# GyroAccelHeaders.net
KiCad netlist of a schematic drawn in Altium Designer
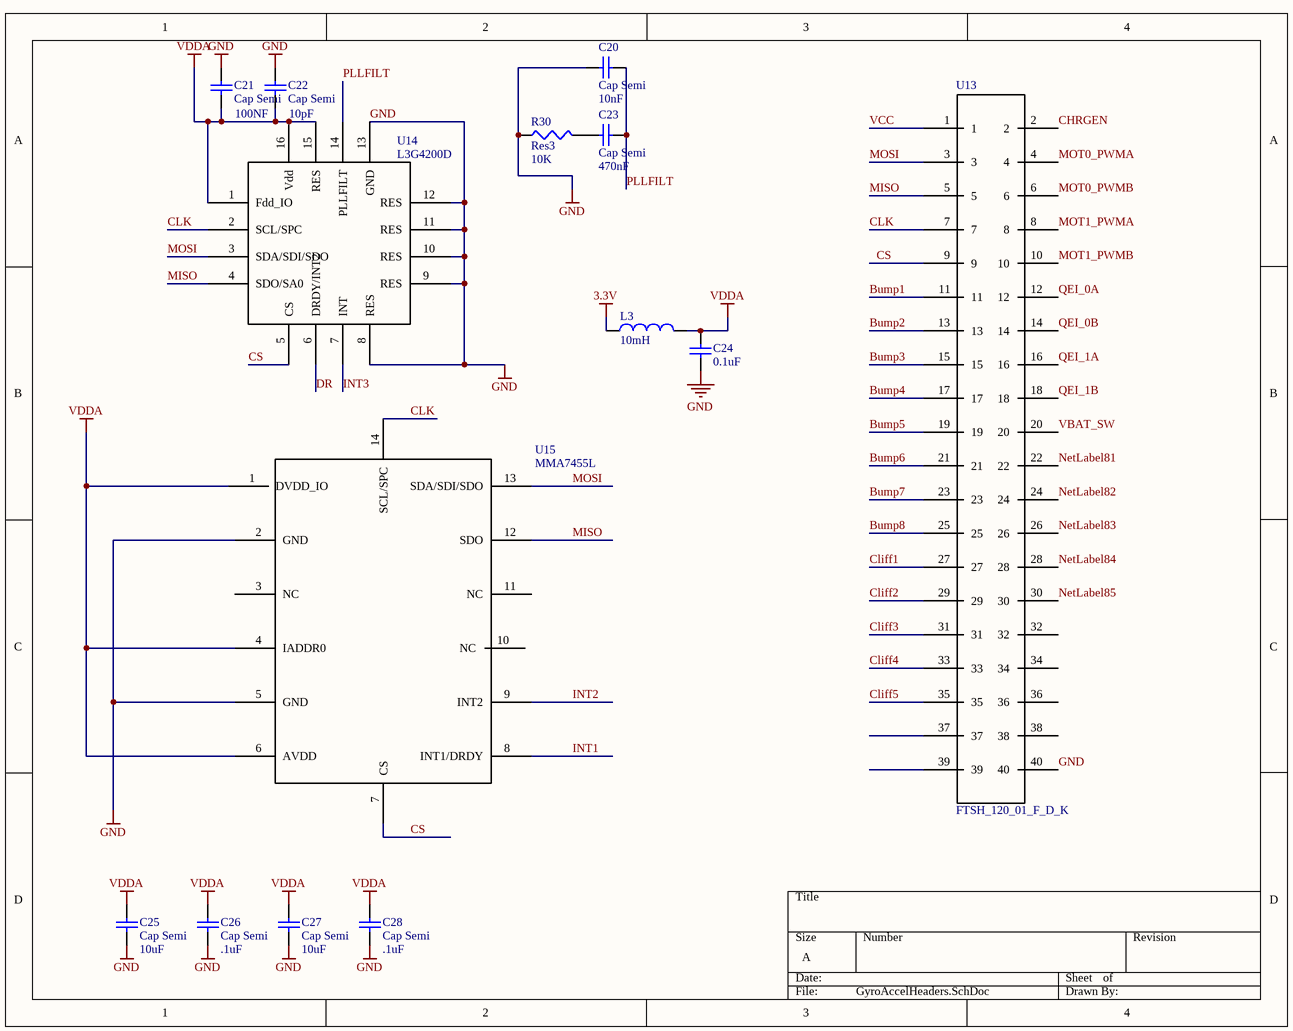
[diagram p0: GyroAccelHeaders.SchDoc]

(export (version "E")
  (design (tool "Eeschema 10.0.6"))
  (components
    (comp (ref "C20")
      (value "Cap Semi")
      (footprint "CAPC3216L")
      (description "Capacitor (Semiconductor SIM Model)")
      (fields (field (name "ALTIUM_VALUE") "10nF") (field (name "PUBLISHER") "Altium Limited"))
      (libsource (lib "Miscellaneous Devices") (part "Cap Semi"))
    )
    (comp (ref "C21")
      (value "Cap Semi")
      (footprint "CAPC3216L")
      (description "Capacitor (Semiconductor SIM Model)")
      (fields (field (name "ALTIUM_VALUE") "100NF") (field (name "PUBLISHER") "Altium Limited"))
      (libsource (lib "Miscellaneous Devices") (part "Cap Semi"))
    )
    (comp (ref "C22")
      (value "Cap Semi")
      (footprint "CAPC3216L")
      (description "Capacitor (Semiconductor SIM Model)")
      (fields (field (name "ALTIUM_VALUE") "10pF") (field (name "PUBLISHER") "Altium Limited"))
      (libsource (lib "Miscellaneous Devices") (part "Cap Semi"))
    )
    (comp (ref "C23")
      (value "Cap Semi")
      (footprint "CAPC3216L")
      (description "Capacitor (Semiconductor SIM Model)")
      (fields (field (name "ALTIUM_VALUE") "470nF") (field (name "PUBLISHER") "Altium Limited"))
      (libsource (lib "Miscellaneous Devices") (part "Cap Semi"))
    )
    (comp (ref "C24")
      (value "0.1uF")
      (footprint "CAPC1005L")
      (description "Capacitor (Semiconductor SIM Model)")
      (fields (field (name "Comment") "Cap Semi") (field (name "PUBLISHER") "Altium Limited"))
      (libsource (lib "Miscellaneous Devices") (part "Cap Semi"))
    )
    (comp (ref "C25")
      (value "Cap Semi")
      (footprint "CAPC3216L")
      (description "Capacitor (Semiconductor SIM Model)")
      (fields (field (name "ALTIUM_VALUE") "10uF") (field (name "PUBLISHER") "Altium Limited"))
      (libsource (lib "Miscellaneous Devices") (part "Cap Semi"))
    )
    (comp (ref "C26")
      (value "Cap Semi")
      (footprint "CAPC3216L")
      (description "Capacitor (Semiconductor SIM Model)")
      (fields (field (name "ALTIUM_VALUE") ".1uF") (field (name "PUBLISHER") "Altium Limited"))
      (libsource (lib "Miscellaneous Devices") (part "Cap Semi"))
    )
    (comp (ref "C27")
      (value "Cap Semi")
      (footprint "CAPC3216L")
      (description "Capacitor (Semiconductor SIM Model)")
      (fields (field (name "ALTIUM_VALUE") "10uF") (field (name "PUBLISHER") "Altium Limited"))
      (libsource (lib "Miscellaneous Devices") (part "Cap Semi"))
    )
    (comp (ref "C28")
      (value "Cap Semi")
      (footprint "CAPC3216L")
      (description "Capacitor (Semiconductor SIM Model)")
      (fields (field (name "ALTIUM_VALUE") ".1uF") (field (name "PUBLISHER") "Altium Limited"))
      (libsource (lib "Miscellaneous Devices") (part "Cap Semi"))
    )
    (comp (ref "L3")
      (value "10mH")
      (footprint "INDC2012L")
      (description "Inductor")
      (fields (field (name "PUBLISHER") "Altium Limited"))
      (libsource (lib "Miscellaneous Devices") (part "Inductor"))
    )
    (comp (ref "R30")
      (value "Res3")
      (footprint "RESC1608L")
      (description "Resistor")
      (fields (field (name "ALTIUM_VALUE") "10K") (field (name "PUBLISHER") "Altium Limited"))
      (libsource (lib "Miscellaneous Devices") (part "Res3"))
    )
    (comp (ref "U13")
      (value "FTSH_120_01_F_D_K")
      (footprint "FTSH_120_01_F_D_K")
      (description "Header, 2X20, 50mil, IDC")
      (libsource (lib "mrone") (part "FTSH_120_01_F_D_K"))
    )
    (comp (ref "U14")
      (value "L3G4200D")
      (footprint "L3G4200D")
      (description "3axis gyroscope, SPI")
      (libsource (lib "mrone") (part "L3G4200D"))
    )
    (comp (ref "U15")
      (value "MMA7455L")
      (footprint "MMA7455L")
      (description "3axis accelerometer")
      (libsource (lib "mrone") (part "MMA7455L"))
    )
  )
  (nets
    (net (code "1") (name "/Bump1") (class "Default")
      (node (ref "U13") (pin "11") (pinfunction "11_11") (pintype "passive"))
    )
    (net (code "2") (name "/Bump2") (class "Default")
      (node (ref "U13") (pin "13") (pinfunction "13_13") (pintype "passive"))
    )
    (net (code "3") (name "/Bump3") (class "Default")
      (node (ref "U13") (pin "15") (pinfunction "15_15") (pintype "passive"))
    )
    (net (code "4") (name "/Bump4") (class "Default")
      (node (ref "U13") (pin "17") (pinfunction "17_17") (pintype "passive"))
    )
    (net (code "5") (name "/Bump5") (class "Default")
      (node (ref "U13") (pin "19") (pinfunction "19_19") (pintype "passive"))
    )
    (net (code "6") (name "/Bump6") (class "Default")
      (node (ref "U13") (pin "21") (pinfunction "21_21") (pintype "passive"))
    )
    (net (code "7") (name "/Bump7") (class "Default")
      (node (ref "U13") (pin "23") (pinfunction "23_23") (pintype "passive"))
    )
    (net (code "8") (name "/Bump8") (class "Default")
      (node (ref "U13") (pin "25") (pinfunction "25_25") (pintype "passive"))
    )
    (net (code "9") (name "/CHRGEN") (class "Default")
      (node (ref "U13") (pin "2") (pinfunction "2_2") (pintype "passive"))
    )
    (net (code "10") (name "/CLK") (class "Default")
      (node (ref "U13") (pin "7") (pinfunction "7_7") (pintype "passive"))
      (node (ref "U14") (pin "2") (pinfunction "SCL/SPC_2") (pintype "passive"))
      (node (ref "U15") (pin "14") (pinfunction "SCL/SPC_14") (pintype "passive"))
    )
    (net (code "11") (name "/CS") (class "Default")
      (node (ref "U13") (pin "9") (pinfunction "9_9") (pintype "passive"))
      (node (ref "U14") (pin "5") (pinfunction "CS_5") (pintype "passive"))
      (node (ref "U15") (pin "7") (pinfunction "CS_7") (pintype "passive"))
    )
    (net (code "12") (name "/Cliff1") (class "Default")
      (node (ref "U13") (pin "27") (pinfunction "27_27") (pintype "passive"))
    )
    (net (code "13") (name "/Cliff2") (class "Default")
      (node (ref "U13") (pin "29") (pinfunction "29_29") (pintype "passive"))
    )
    (net (code "14") (name "/Cliff3") (class "Default")
      (node (ref "U13") (pin "31") (pinfunction "31_31") (pintype "passive"))
    )
    (net (code "15") (name "/Cliff4") (class "Default")
      (node (ref "U13") (pin "33") (pinfunction "33_33") (pintype "passive"))
    )
    (net (code "16") (name "/Cliff5") (class "Default")
      (node (ref "U13") (pin "35") (pinfunction "35_35") (pintype "passive"))
    )
    (net (code "17") (name "/DR") (class "Default")
      (node (ref "U14") (pin "6") (pinfunction "DRDY/INT2_6") (pintype "passive"))
    )
    (net (code "18") (name "/INT1") (class "Default")
      (node (ref "U15") (pin "8") (pinfunction "INT1/DRDY_8") (pintype "passive"))
    )
    (net (code "19") (name "/INT2") (class "Default")
      (node (ref "U15") (pin "9") (pinfunction "INT2_9") (pintype "passive"))
    )
    (net (code "20") (name "/INT3") (class "Default")
      (node (ref "U14") (pin "7") (pinfunction "INT_7") (pintype "passive"))
    )
    (net (code "21") (name "/MISO") (class "Default")
      (node (ref "U13") (pin "5") (pinfunction "5_5") (pintype "passive"))
      (node (ref "U14") (pin "4") (pinfunction "SDO/SA0_4") (pintype "passive"))
      (node (ref "U15") (pin "12") (pinfunction "SDO_12") (pintype "passive"))
    )
    (net (code "22") (name "/MOSI") (class "Default")
      (node (ref "U13") (pin "3") (pinfunction "3_3") (pintype "passive"))
      (node (ref "U14") (pin "3") (pinfunction "SDA/SDI/SDO_3") (pintype "passive"))
      (node (ref "U15") (pin "13") (pinfunction "SDA/SDI/SDO_13") (pintype "passive"))
    )
    (net (code "23") (name "/MOT0_PWMA") (class "Default")
      (node (ref "U13") (pin "4") (pinfunction "4_4") (pintype "passive"))
    )
    (net (code "24") (name "/MOT0_PWMB") (class "Default")
      (node (ref "U13") (pin "6") (pinfunction "6_6") (pintype "passive"))
    )
    (net (code "25") (name "/MOT1_PWMA") (class "Default")
      (node (ref "U13") (pin "8") (pinfunction "8_8") (pintype "passive"))
    )
    (net (code "26") (name "/MOT1_PWMB") (class "Default")
      (node (ref "U13") (pin "10") (pinfunction "10_10") (pintype "passive"))
    )
    (net (code "27") (name "/NetLabel81") (class "Default")
      (node (ref "U13") (pin "22") (pinfunction "22_22") (pintype "passive"))
    )
    (net (code "28") (name "/NetLabel82") (class "Default")
      (node (ref "U13") (pin "24") (pinfunction "24_24") (pintype "passive"))
    )
    (net (code "29") (name "/NetLabel83") (class "Default")
      (node (ref "U13") (pin "26") (pinfunction "26_26") (pintype "passive"))
    )
    (net (code "30") (name "/NetLabel84") (class "Default")
      (node (ref "U13") (pin "28") (pinfunction "28_28") (pintype "passive"))
    )
    (net (code "31") (name "/NetLabel85") (class "Default")
      (node (ref "U13") (pin "30") (pinfunction "30_30") (pintype "passive"))
    )
    (net (code "32") (name "/PLLFILT") (class "Default")
      (node (ref "C20") (pin "2") (pinfunction "2_2") (pintype "passive"))
      (node (ref "C23") (pin "2") (pinfunction "2_2") (pintype "passive"))
      (node (ref "U14") (pin "14") (pinfunction "PLLFILT_14") (pintype "passive"))
    )
    (net (code "33") (name "/QEI_0A") (class "Default")
      (node (ref "U13") (pin "12") (pinfunction "12_12") (pintype "passive"))
    )
    (net (code "34") (name "/QEI_0B") (class "Default")
      (node (ref "U13") (pin "14") (pinfunction "14_14") (pintype "passive"))
    )
    (net (code "35") (name "/QEI_1A") (class "Default")
      (node (ref "U13") (pin "16") (pinfunction "16_16") (pintype "passive"))
    )
    (net (code "36") (name "/QEI_1B") (class "Default")
      (node (ref "U13") (pin "18") (pinfunction "18_18") (pintype "passive"))
    )
    (net (code "37") (name "/VBAT_SW") (class "Default")
      (node (ref "U13") (pin "20") (pinfunction "20_20") (pintype "passive"))
    )
    (net (code "38") (name "/VCC") (class "Default")
      (node (ref "U13") (pin "1") (pinfunction "1_1") (pintype "passive"))
    )
    (net (code "39") (name "3.3V") (class "Default")
      (node (ref "L3") (pin "2") (pinfunction "2_2") (pintype "passive"))
    )
    (net (code "40") (name "GND") (class "Default")
      (node (ref "C20") (pin "1") (pinfunction "1_1") (pintype "passive"))
      (node (ref "C21") (pin "2") (pinfunction "2_2") (pintype "passive"))
      (node (ref "C22") (pin "2") (pinfunction "2_2") (pintype "passive"))
      (node (ref "C24") (pin "1") (pinfunction "1_1") (pintype "passive"))
      (node (ref "C25") (pin "1") (pinfunction "1_1") (pintype "passive"))
      (node (ref "C26") (pin "1") (pinfunction "1_1") (pintype "passive"))
      (node (ref "C27") (pin "1") (pinfunction "1_1") (pintype "passive"))
      (node (ref "C28") (pin "1") (pinfunction "1_1") (pintype "passive"))
      (node (ref "R30") (pin "1") (pinfunction "1_1") (pintype "passive"))
      (node (ref "U13") (pin "40") (pinfunction "40_40") (pintype "passive"))
      (node (ref "U14") (pin "10") (pinfunction "RES_10") (pintype "passive"))
      (node (ref "U14") (pin "11") (pinfunction "RES_11") (pintype "passive"))
      (node (ref "U14") (pin "12") (pinfunction "RES_12") (pintype "passive"))
      (node (ref "U14") (pin "13") (pinfunction "GND_13") (pintype "passive"))
      (node (ref "U14") (pin "8") (pinfunction "RES_8") (pintype "passive"))
      (node (ref "U14") (pin "9") (pinfunction "RES_9") (pintype "passive"))
      (node (ref "U15") (pin "2") (pinfunction "GND_2") (pintype "passive"))
      (node (ref "U15") (pin "5") (pinfunction "GND_5") (pintype "passive"))
    )
    (net (code "41") (name "Net-(C23-Pad1)") (class "Default")
      (node (ref "C23") (pin "1") (pinfunction "1_1") (pintype "passive"))
      (node (ref "R30") (pin "2") (pinfunction "2_2") (pintype "passive"))
    )
    (net (code "42") (name "VDDA") (class "Default")
      (node (ref "C21") (pin "1") (pinfunction "1_1") (pintype "passive"))
      (node (ref "C22") (pin "1") (pinfunction "1_1") (pintype "passive"))
      (node (ref "C24") (pin "2") (pinfunction "2_2") (pintype "passive"))
      (node (ref "C25") (pin "2") (pinfunction "2_2") (pintype "passive"))
      (node (ref "C26") (pin "2") (pinfunction "2_2") (pintype "passive"))
      (node (ref "C27") (pin "2") (pinfunction "2_2") (pintype "passive"))
      (node (ref "C28") (pin "2") (pinfunction "2_2") (pintype "passive"))
      (node (ref "L3") (pin "1") (pinfunction "1_1") (pintype "passive"))
      (node (ref "U14") (pin "1") (pinfunction "Fdd_IO_1") (pintype "passive"))
      (node (ref "U14") (pin "15") (pinfunction "RES_15") (pintype "passive"))
      (node (ref "U14") (pin "16") (pinfunction "Vdd_16") (pintype "passive"))
      (node (ref "U15") (pin "1") (pinfunction "DVDD_IO_1") (pintype "passive"))
      (node (ref "U15") (pin "4") (pinfunction "IADDR0_4") (pintype "passive"))
      (node (ref "U15") (pin "6") (pinfunction "AVDD_6") (pintype "passive"))
    )
    (net (code "43") (name "unconnected-(U13-Pad32)") (class "Default")
      (node (ref "U13") (pin "32") (pinfunction "32_32") (pintype "passive"))
    )
    (net (code "44") (name "unconnected-(U13-Pad34)") (class "Default")
      (node (ref "U13") (pin "34") (pinfunction "34_34") (pintype "passive"))
    )
    (net (code "45") (name "unconnected-(U13-Pad36)") (class "Default")
      (node (ref "U13") (pin "36") (pinfunction "36_36") (pintype "passive"))
    )
    (net (code "46") (name "unconnected-(U13-Pad37)") (class "Default")
      (node (ref "U13") (pin "37") (pinfunction "37_37") (pintype "passive"))
    )
    (net (code "47") (name "unconnected-(U13-Pad38)") (class "Default")
      (node (ref "U13") (pin "38") (pinfunction "38_38") (pintype "passive"))
    )
    (net (code "48") (name "unconnected-(U13-Pad39)") (class "Default")
      (node (ref "U13") (pin "39") (pinfunction "39_39") (pintype "passive"))
    )
    (net (code "49") (name "unconnected-(U15-NC-Pad3)") (class "Default")
      (node (ref "U15") (pin "3") (pinfunction "NC_3") (pintype "passive"))
    )
    (net (code "50") (name "unconnected-(U15-NC-Pad10)") (class "Default")
      (node (ref "U15") (pin "10") (pinfunction "NC_10") (pintype "passive"))
    )
    (net (code "51") (name "unconnected-(U15-NC-Pad11)") (class "Default")
      (node (ref "U15") (pin "11") (pinfunction "NC_11") (pintype "passive"))
    )
  )
)
